# eMMC.net
KiCad netlist of a schematic drawn in Altium Designer
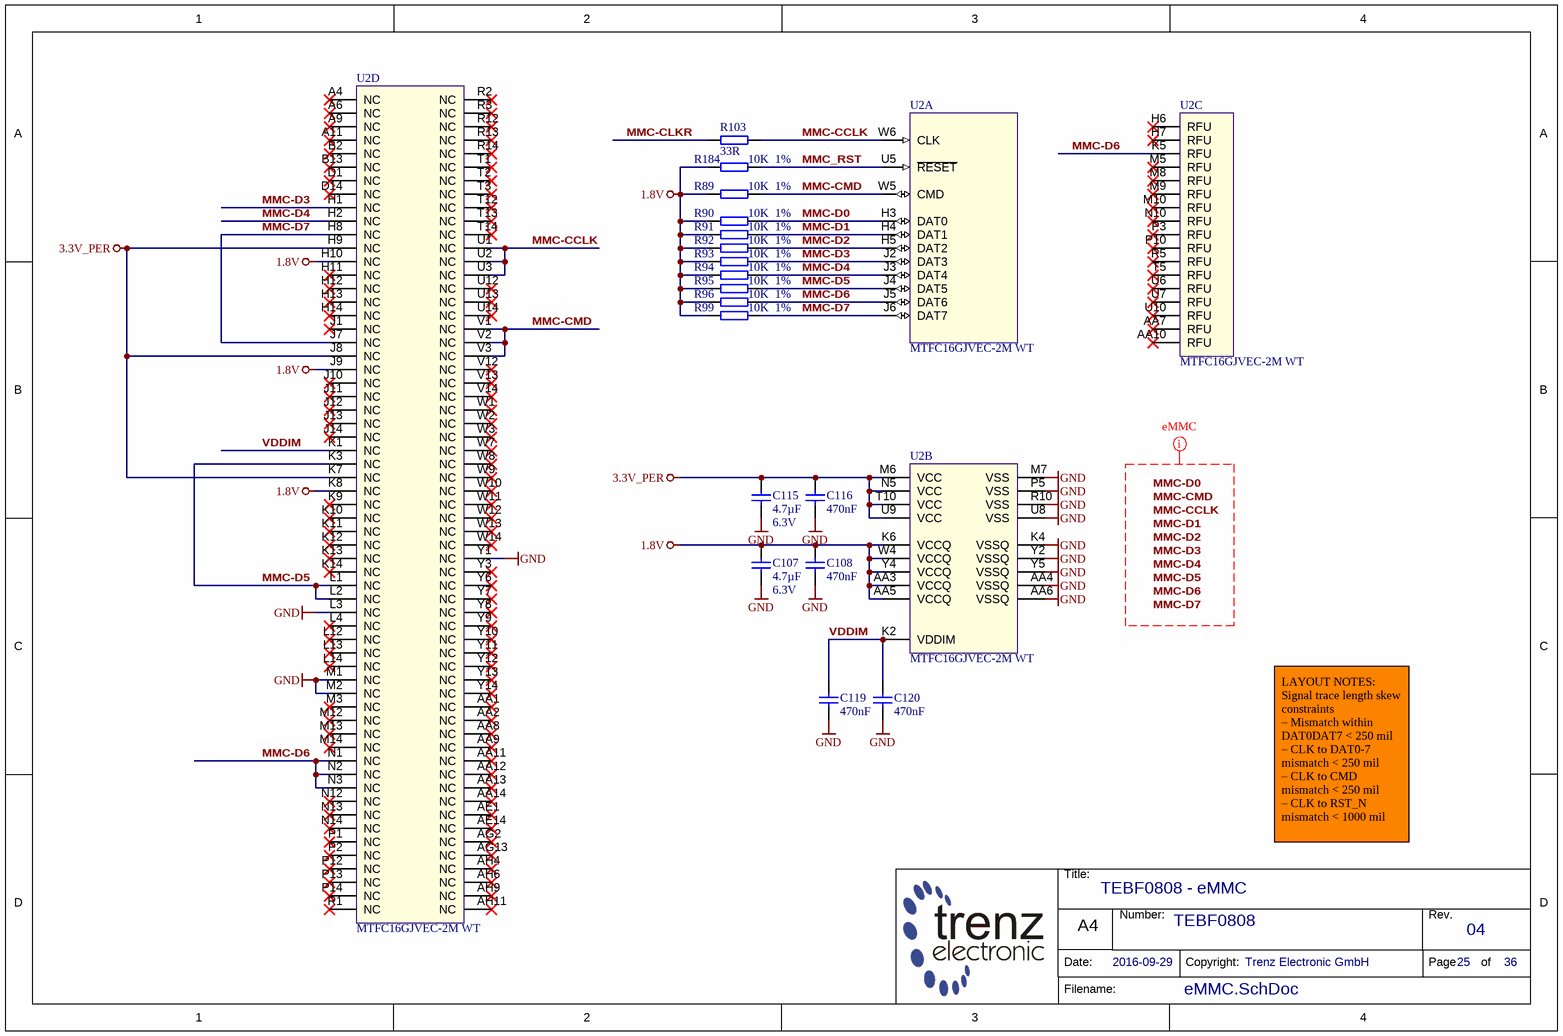
[diagram p0: eMMC.SchDoc]

(export (version "E")
  (design (tool "Eeschema 10.0.6"))
  (components
    (comp (ref "C107")
      (value "4.7µF")
      (footprint "CAPC1005X60N")
      (description "KON 4.7µF 6.3V X5R SMD 20%")
      (fields (field (name "VOLTAGE") "6.3V") (field (name "TOLERANCE") "20%"))
      (libsource (lib "TE") (part "CAP-NP"))
    )
    (comp (ref "C108")
      (value "470nF")
      (footprint "CAPC1005X55N")
      (description "KON 470nF 6,3V X5R SMD")
      (fields (field (name "VOLTAGE") "6.3V"))
      (libsource (lib "TE") (part "CAP-NP"))
    )
    (comp (ref "C115")
      (value "4.7µF")
      (footprint "CAPC1005X60N")
      (description "KON 4.7µF 6.3V X5R SMD 20%")
      (fields (field (name "VOLTAGE") "6.3V") (field (name "TOLERANCE") "20%"))
      (libsource (lib "TE") (part "CAP-NP"))
    )
    (comp (ref "C116")
      (value "470nF")
      (footprint "CAPC1005X55N")
      (description "KON 470nF 6,3V X5R SMD")
      (fields (field (name "VOLTAGE") "6.3V"))
      (libsource (lib "TE") (part "CAP-NP"))
    )
    (comp (ref "C119")
      (value "470nF")
      (footprint "CAPC1005X55N")
      (description "KON 470nF 6,3V X5R SMD")
      (fields (field (name "VOLTAGE") "6.3V"))
      (libsource (lib "TE") (part "CAP-NP"))
    )
    (comp (ref "C120")
      (value "470nF")
      (footprint "CAPC1005X55N")
      (description "KON 470nF 6,3V X5R SMD")
      (fields (field (name "VOLTAGE") "6.3V"))
      (libsource (lib "TE") (part "CAP-NP"))
    )
    (comp (ref "R89")
      (value "10K")
      (footprint "RESC1005X40N")
      (description "WID SMD 10K 1% 0,063W")
      (fields (field (name "TOLERANCE") "1%"))
      (libsource (lib "TE") (part "RES"))
    )
    (comp (ref "R90")
      (value "10K")
      (footprint "RESC1005X40N")
      (description "WID SMD 10K 1% 0,063W")
      (fields (field (name "TOLERANCE") "1%"))
      (libsource (lib "TE") (part "RES"))
    )
    (comp (ref "R91")
      (value "10K")
      (footprint "RESC1005X40N")
      (description "WID SMD 10K 1% 0,063W")
      (fields (field (name "TOLERANCE") "1%"))
      (libsource (lib "TE") (part "RES"))
    )
    (comp (ref "R92")
      (value "10K")
      (footprint "RESC1005X40N")
      (description "WID SMD 10K 1% 0,063W")
      (fields (field (name "TOLERANCE") "1%"))
      (libsource (lib "TE") (part "RES"))
    )
    (comp (ref "R93")
      (value "10K")
      (footprint "RESC1005X40N")
      (description "WID SMD 10K 1% 0,063W")
      (fields (field (name "TOLERANCE") "1%"))
      (libsource (lib "TE") (part "RES"))
    )
    (comp (ref "R94")
      (value "10K")
      (footprint "RESC1005X40N")
      (description "WID SMD 10K 1% 0,063W")
      (fields (field (name "TOLERANCE") "1%"))
      (libsource (lib "TE") (part "RES"))
    )
    (comp (ref "R95")
      (value "10K")
      (footprint "RESC1005X40N")
      (description "WID SMD 10K 1% 0,063W")
      (fields (field (name "TOLERANCE") "1%"))
      (libsource (lib "TE") (part "RES"))
    )
    (comp (ref "R96")
      (value "10K")
      (footprint "RESC1005X40N")
      (description "WID SMD 10K 1% 0,063W")
      (fields (field (name "TOLERANCE") "1%"))
      (libsource (lib "TE") (part "RES"))
    )
    (comp (ref "R99")
      (value "10K")
      (footprint "RESC1005X40N")
      (description "WID SMD 10K 1% 0,063W")
      (fields (field (name "TOLERANCE") "1%"))
      (libsource (lib "TE") (part "RES"))
    )
    (comp (ref "R103")
      (value "33R")
      (footprint "RESC1005X40N")
      (description "WID SMD 33R 1% 0,063W")
      (fields (field (name "TOLERANCE") "1%"))
      (libsource (lib "TE") (part "RES"))
    )
    (comp (ref "R184")
      (value "10K")
      (footprint "RESC1005X40N")
      (description "WID SMD 10K 1% 0,063W")
      (fields (field (name "TOLERANCE") "1%"))
      (libsource (lib "TE") (part "RES"))
    )
    (comp (ref "U2")
      (value "MTFC16GJVEC-2M WT")
      (footprint "BGA169C50P14X28_1400X1800X80_MICRON")
      (libsource (lib "TE") (part "MTFC-WFBGA169"))
    )
  )
  (nets
    (net (code "1") (name "/MMC-CCLK") (class "Default")
      (node (ref "R103") (pin "2") (pinfunction "2_2") (pintype "passive"))
      (node (ref "U2") (pin "U1") (pinfunction "NC_U1") (pintype "passive"))
      (node (ref "U2") (pin "U2") (pinfunction "NC_U2") (pintype "passive"))
      (node (ref "U2") (pin "U3") (pinfunction "NC_U3") (pintype "passive"))
      (node (ref "U2") (pin "W6") (pinfunction "CLK_W6") (pintype "input"))
    )
    (net (code "2") (name "/MMC-CLKR") (class "Default")
      (node (ref "R103") (pin "1") (pinfunction "1_1") (pintype "passive"))
    )
    (net (code "3") (name "/MMC-CMD") (class "Default")
      (node (ref "R89") (pin "2") (pinfunction "2_2") (pintype "passive"))
      (node (ref "U2") (pin "V1") (pinfunction "NC_V1") (pintype "passive"))
      (node (ref "U2") (pin "V2") (pinfunction "NC_V2") (pintype "passive"))
      (node (ref "U2") (pin "V3") (pinfunction "NC_V3") (pintype "passive"))
      (node (ref "U2") (pin "W5") (pinfunction "CMD_W5") (pintype "bidirectional"))
    )
    (net (code "4") (name "/MMC-D0") (class "Default")
      (node (ref "R90") (pin "2") (pinfunction "2_2") (pintype "passive"))
      (node (ref "U2") (pin "H3") (pinfunction "DAT0_H3") (pintype "bidirectional"))
    )
    (net (code "5") (name "/MMC-D1") (class "Default")
      (node (ref "R91") (pin "2") (pinfunction "2_2") (pintype "passive"))
      (node (ref "U2") (pin "H4") (pinfunction "DAT1_H4") (pintype "bidirectional"))
    )
    (net (code "6") (name "/MMC-D2") (class "Default")
      (node (ref "R92") (pin "2") (pinfunction "2_2") (pintype "passive"))
      (node (ref "U2") (pin "H5") (pinfunction "DAT2_H5") (pintype "bidirectional"))
    )
    (net (code "7") (name "/MMC-D3") (class "Default")
      (node (ref "R93") (pin "2") (pinfunction "2_2") (pintype "passive"))
      (node (ref "U2") (pin "H1") (pinfunction "NC_H1") (pintype "passive"))
      (node (ref "U2") (pin "J2") (pinfunction "DAT3_J2") (pintype "bidirectional"))
    )
    (net (code "8") (name "/MMC-D4") (class "Default")
      (node (ref "R94") (pin "2") (pinfunction "2_2") (pintype "passive"))
      (node (ref "U2") (pin "H2") (pinfunction "NC_H2") (pintype "passive"))
      (node (ref "U2") (pin "J3") (pinfunction "DAT4_J3") (pintype "bidirectional"))
    )
    (net (code "9") (name "/MMC-D5") (class "Default")
      (node (ref "R95") (pin "2") (pinfunction "2_2") (pintype "passive"))
      (node (ref "U2") (pin "J4") (pinfunction "DAT5_J4") (pintype "bidirectional"))
      (node (ref "U2") (pin "K3") (pinfunction "NC_K3") (pintype "passive"))
      (node (ref "U2") (pin "L1") (pinfunction "NC_L1") (pintype "passive"))
      (node (ref "U2") (pin "L2") (pinfunction "NC_L2") (pintype "passive"))
    )
    (net (code "10") (name "/MMC-D6") (class "Default")
      (node (ref "R96") (pin "2") (pinfunction "2_2") (pintype "passive"))
      (node (ref "U2") (pin "J5") (pinfunction "DAT6_J5") (pintype "bidirectional"))
      (node (ref "U2") (pin "K5") (pinfunction "RFU_K5") (pintype "passive"))
      (node (ref "U2") (pin "N1") (pinfunction "NC_N1") (pintype "passive"))
      (node (ref "U2") (pin "N2") (pinfunction "NC_N2") (pintype "passive"))
      (node (ref "U2") (pin "N3") (pinfunction "NC_N3") (pintype "passive"))
    )
    (net (code "11") (name "/MMC-D7") (class "Default")
      (node (ref "R99") (pin "2") (pinfunction "2_2") (pintype "passive"))
      (node (ref "U2") (pin "H8") (pinfunction "NC_H8") (pintype "passive"))
      (node (ref "U2") (pin "J6") (pinfunction "DAT7_J6") (pintype "bidirectional"))
      (node (ref "U2") (pin "J7") (pinfunction "NC_J7") (pintype "passive"))
    )
    (net (code "12") (name "/MMC_RST") (class "Default")
      (node (ref "R184") (pin "2") (pinfunction "2_2") (pintype "passive"))
      (node (ref "U2") (pin "U5") (pinfunction "~{RESET}_U5") (pintype "input"))
    )
    (net (code "13") (name "/VDDIM") (class "Default")
      (node (ref "C119") (pin "1") (pinfunction "1_1") (pintype "passive"))
      (node (ref "C120") (pin "1") (pinfunction "1_1") (pintype "passive"))
      (node (ref "U2") (pin "K1") (pinfunction "NC_K1") (pintype "passive"))
      (node (ref "U2") (pin "K2") (pinfunction "VDDIM_K2") (pintype "power_in"))
    )
    (net (code "14") (name "1.8V") (class "Default")
      (node (ref "C107") (pin "1") (pinfunction "1_1") (pintype "passive"))
      (node (ref "C108") (pin "1") (pinfunction "1_1") (pintype "passive"))
      (node (ref "R184") (pin "1") (pinfunction "1_1") (pintype "passive"))
      (node (ref "R89") (pin "1") (pinfunction "1_1") (pintype "passive"))
      (node (ref "R90") (pin "1") (pinfunction "1_1") (pintype "passive"))
      (node (ref "R91") (pin "1") (pinfunction "1_1") (pintype "passive"))
      (node (ref "R92") (pin "1") (pinfunction "1_1") (pintype "passive"))
      (node (ref "R93") (pin "1") (pinfunction "1_1") (pintype "passive"))
      (node (ref "R94") (pin "1") (pinfunction "1_1") (pintype "passive"))
      (node (ref "R95") (pin "1") (pinfunction "1_1") (pintype "passive"))
      (node (ref "R96") (pin "1") (pinfunction "1_1") (pintype "passive"))
      (node (ref "R99") (pin "1") (pinfunction "1_1") (pintype "passive"))
      (node (ref "U2") (pin "AA3") (pinfunction "VCCQ_AA3") (pintype "power_in"))
      (node (ref "U2") (pin "AA5") (pinfunction "VCCQ_AA5") (pintype "power_in"))
      (node (ref "U2") (pin "H10") (pinfunction "NC_H10") (pintype "passive"))
      (node (ref "U2") (pin "J9") (pinfunction "NC_J9") (pintype "passive"))
      (node (ref "U2") (pin "K6") (pinfunction "VCCQ_K6") (pintype "power_in"))
      (node (ref "U2") (pin "K8") (pinfunction "NC_K8") (pintype "passive"))
      (node (ref "U2") (pin "W4") (pinfunction "VCCQ_W4") (pintype "power_in"))
      (node (ref "U2") (pin "Y4") (pinfunction "VCCQ_Y4") (pintype "power_in"))
    )
    (net (code "15") (name "3.3V_PER") (class "Default")
      (node (ref "C115") (pin "1") (pinfunction "1_1") (pintype "passive"))
      (node (ref "C116") (pin "1") (pinfunction "1_1") (pintype "passive"))
      (node (ref "U2") (pin "H9") (pinfunction "NC_H9") (pintype "passive"))
      (node (ref "U2") (pin "J8") (pinfunction "NC_J8") (pintype "passive"))
      (node (ref "U2") (pin "K7") (pinfunction "NC_K7") (pintype "passive"))
      (node (ref "U2") (pin "M6") (pinfunction "VCC_M6") (pintype "power_in"))
      (node (ref "U2") (pin "N5") (pinfunction "VCC_N5") (pintype "power_in"))
      (node (ref "U2") (pin "T10") (pinfunction "VCC_T10") (pintype "power_in"))
      (node (ref "U2") (pin "U9") (pinfunction "VCC_U9") (pintype "power_in"))
    )
    (net (code "16") (name "GND") (class "Default")
      (node (ref "C107") (pin "2") (pinfunction "2_2") (pintype "passive"))
      (node (ref "C108") (pin "2") (pinfunction "2_2") (pintype "passive"))
      (node (ref "C115") (pin "2") (pinfunction "2_2") (pintype "passive"))
      (node (ref "C116") (pin "2") (pinfunction "2_2") (pintype "passive"))
      (node (ref "C119") (pin "2") (pinfunction "2_2") (pintype "passive"))
      (node (ref "C120") (pin "2") (pinfunction "2_2") (pintype "passive"))
      (node (ref "U2") (pin "AA4") (pinfunction "VSSQ_AA4") (pintype "power_in"))
      (node (ref "U2") (pin "AA6") (pinfunction "VSSQ_AA6") (pintype "power_in"))
      (node (ref "U2") (pin "K4") (pinfunction "VSSQ_K4") (pintype "power_in"))
      (node (ref "U2") (pin "L3") (pinfunction "NC_L3") (pintype "passive"))
      (node (ref "U2") (pin "M1") (pinfunction "NC_M1") (pintype "passive"))
      (node (ref "U2") (pin "M2") (pinfunction "NC_M2") (pintype "passive"))
      (node (ref "U2") (pin "M7") (pinfunction "VSS_M7") (pintype "power_in"))
      (node (ref "U2") (pin "P5") (pinfunction "VSS_P5") (pintype "power_in"))
      (node (ref "U2") (pin "R10") (pinfunction "VSS_R10") (pintype "power_in"))
      (node (ref "U2") (pin "U8") (pinfunction "VSS_U8") (pintype "power_in"))
      (node (ref "U2") (pin "Y1") (pinfunction "NC_Y1") (pintype "passive"))
      (node (ref "U2") (pin "Y2") (pinfunction "VSSQ_Y2") (pintype "power_in"))
      (node (ref "U2") (pin "Y5") (pinfunction "VSSQ_Y5") (pintype "power_in"))
    )
    (net (code "17") (name "unconnected-(U2C-RFU-PadAA7)") (class "Default")
      (node (ref "U2") (pin "AA7") (pinfunction "RFU_AA7") (pintype "passive+no_connect"))
    )
    (net (code "18") (name "unconnected-(U2C-RFU-PadAA10)") (class "Default")
      (node (ref "U2") (pin "AA10") (pinfunction "RFU_AA10") (pintype "passive+no_connect"))
    )
    (net (code "19") (name "unconnected-(U2C-RFU-PadH6)") (class "Default")
      (node (ref "U2") (pin "H6") (pinfunction "RFU_H6") (pintype "passive+no_connect"))
    )
    (net (code "20") (name "unconnected-(U2C-RFU-PadH7)") (class "Default")
      (node (ref "U2") (pin "H7") (pinfunction "RFU_H7") (pintype "passive+no_connect"))
    )
    (net (code "21") (name "unconnected-(U2C-RFU-PadM5)") (class "Default")
      (node (ref "U2") (pin "M5") (pinfunction "RFU_M5") (pintype "passive+no_connect"))
    )
    (net (code "22") (name "unconnected-(U2C-RFU-PadM8)") (class "Default")
      (node (ref "U2") (pin "M8") (pinfunction "RFU_M8") (pintype "passive+no_connect"))
    )
    (net (code "23") (name "unconnected-(U2C-RFU-PadM9)") (class "Default")
      (node (ref "U2") (pin "M9") (pinfunction "RFU_M9") (pintype "passive+no_connect"))
    )
    (net (code "24") (name "unconnected-(U2C-RFU-PadM10)") (class "Default")
      (node (ref "U2") (pin "M10") (pinfunction "RFU_M10") (pintype "passive+no_connect"))
    )
    (net (code "25") (name "unconnected-(U2C-RFU-PadN10)") (class "Default")
      (node (ref "U2") (pin "N10") (pinfunction "RFU_N10") (pintype "passive+no_connect"))
    )
    (net (code "26") (name "unconnected-(U2C-RFU-PadP3)") (class "Default")
      (node (ref "U2") (pin "P3") (pinfunction "RFU_P3") (pintype "passive+no_connect"))
    )
    (net (code "27") (name "unconnected-(U2C-RFU-PadP10)") (class "Default")
      (node (ref "U2") (pin "P10") (pinfunction "RFU_P10") (pintype "passive+no_connect"))
    )
    (net (code "28") (name "unconnected-(U2C-RFU-PadR5)") (class "Default")
      (node (ref "U2") (pin "R5") (pinfunction "RFU_R5") (pintype "passive+no_connect"))
    )
    (net (code "29") (name "unconnected-(U2C-RFU-PadT5)") (class "Default")
      (node (ref "U2") (pin "T5") (pinfunction "RFU_T5") (pintype "passive+no_connect"))
    )
    (net (code "30") (name "unconnected-(U2C-RFU-PadU6)") (class "Default")
      (node (ref "U2") (pin "U6") (pinfunction "RFU_U6") (pintype "passive+no_connect"))
    )
    (net (code "31") (name "unconnected-(U2C-RFU-PadU7)") (class "Default")
      (node (ref "U2") (pin "U7") (pinfunction "RFU_U7") (pintype "passive+no_connect"))
    )
    (net (code "32") (name "unconnected-(U2C-RFU-PadU10)") (class "Default")
      (node (ref "U2") (pin "U10") (pinfunction "RFU_U10") (pintype "passive+no_connect"))
    )
    (net (code "33") (name "unconnected-(U2D-NC-PadA4)") (class "Default")
      (node (ref "U2") (pin "A4") (pinfunction "NC_A4") (pintype "passive+no_connect"))
    )
    (net (code "34") (name "unconnected-(U2D-NC-PadA6)") (class "Default")
      (node (ref "U2") (pin "A6") (pinfunction "NC_A6") (pintype "passive+no_connect"))
    )
    (net (code "35") (name "unconnected-(U2D-NC-PadA9)") (class "Default")
      (node (ref "U2") (pin "A9") (pinfunction "NC_A9") (pintype "passive+no_connect"))
    )
    (net (code "36") (name "unconnected-(U2D-NC-PadA11)") (class "Default")
      (node (ref "U2") (pin "A11") (pinfunction "NC_A11") (pintype "passive+no_connect"))
    )
    (net (code "37") (name "unconnected-(U2D-NC-PadAA1)") (class "Default")
      (node (ref "U2") (pin "AA1") (pinfunction "NC_AA1") (pintype "passive+no_connect"))
    )
    (net (code "38") (name "unconnected-(U2D-NC-PadAA2)") (class "Default")
      (node (ref "U2") (pin "AA2") (pinfunction "NC_AA2") (pintype "passive+no_connect"))
    )
    (net (code "39") (name "unconnected-(U2D-NC-PadAA8)") (class "Default")
      (node (ref "U2") (pin "AA8") (pinfunction "NC_AA8") (pintype "passive+no_connect"))
    )
    (net (code "40") (name "unconnected-(U2D-NC-PadAA9)") (class "Default")
      (node (ref "U2") (pin "AA9") (pinfunction "NC_AA9") (pintype "passive+no_connect"))
    )
    (net (code "41") (name "unconnected-(U2D-NC-PadAA11)") (class "Default")
      (node (ref "U2") (pin "AA11") (pinfunction "NC_AA11") (pintype "passive+no_connect"))
    )
    (net (code "42") (name "unconnected-(U2D-NC-PadAA12)") (class "Default")
      (node (ref "U2") (pin "AA12") (pinfunction "NC_AA12") (pintype "passive+no_connect"))
    )
    (net (code "43") (name "unconnected-(U2D-NC-PadAA13)") (class "Default")
      (node (ref "U2") (pin "AA13") (pinfunction "NC_AA13") (pintype "passive+no_connect"))
    )
    (net (code "44") (name "unconnected-(U2D-NC-PadAA14)") (class "Default")
      (node (ref "U2") (pin "AA14") (pinfunction "NC_AA14") (pintype "passive+no_connect"))
    )
    (net (code "45") (name "unconnected-(U2D-NC-PadAE1)") (class "Default")
      (node (ref "U2") (pin "AE1") (pinfunction "NC_AE1") (pintype "passive+no_connect"))
    )
    (net (code "46") (name "unconnected-(U2D-NC-PadAE14)") (class "Default")
      (node (ref "U2") (pin "AE14") (pinfunction "NC_AE14") (pintype "passive+no_connect"))
    )
    (net (code "47") (name "unconnected-(U2D-NC-PadAG2)") (class "Default")
      (node (ref "U2") (pin "AG2") (pinfunction "NC_AG2") (pintype "passive+no_connect"))
    )
    (net (code "48") (name "unconnected-(U2D-NC-PadAG13)") (class "Default")
      (node (ref "U2") (pin "AG13") (pinfunction "NC_AG13") (pintype "passive+no_connect"))
    )
    (net (code "49") (name "unconnected-(U2D-NC-PadAH4)") (class "Default")
      (node (ref "U2") (pin "AH4") (pinfunction "NC_AH4") (pintype "passive+no_connect"))
    )
    (net (code "50") (name "unconnected-(U2D-NC-PadAH6)") (class "Default")
      (node (ref "U2") (pin "AH6") (pinfunction "NC_AH6") (pintype "passive+no_connect"))
    )
    (net (code "51") (name "unconnected-(U2D-NC-PadAH9)") (class "Default")
      (node (ref "U2") (pin "AH9") (pinfunction "NC_AH9") (pintype "passive+no_connect"))
    )
    (net (code "52") (name "unconnected-(U2D-NC-PadAH11)") (class "Default")
      (node (ref "U2") (pin "AH11") (pinfunction "NC_AH11") (pintype "passive+no_connect"))
    )
    (net (code "53") (name "unconnected-(U2D-NC-PadB2)") (class "Default")
      (node (ref "U2") (pin "B2") (pinfunction "NC_B2") (pintype "passive+no_connect"))
    )
    (net (code "54") (name "unconnected-(U2D-NC-PadB13)") (class "Default")
      (node (ref "U2") (pin "B13") (pinfunction "NC_B13") (pintype "passive+no_connect"))
    )
    (net (code "55") (name "unconnected-(U2D-NC-PadD1)") (class "Default")
      (node (ref "U2") (pin "D1") (pinfunction "NC_D1") (pintype "passive+no_connect"))
    )
    (net (code "56") (name "unconnected-(U2D-NC-PadD14)") (class "Default")
      (node (ref "U2") (pin "D14") (pinfunction "NC_D14") (pintype "passive+no_connect"))
    )
    (net (code "57") (name "unconnected-(U2D-NC-PadH11)") (class "Default")
      (node (ref "U2") (pin "H11") (pinfunction "NC_H11") (pintype "passive+no_connect"))
    )
    (net (code "58") (name "unconnected-(U2D-NC-PadH12)") (class "Default")
      (node (ref "U2") (pin "H12") (pinfunction "NC_H12") (pintype "passive+no_connect"))
    )
    (net (code "59") (name "unconnected-(U2D-NC-PadH13)") (class "Default")
      (node (ref "U2") (pin "H13") (pinfunction "NC_H13") (pintype "passive+no_connect"))
    )
    (net (code "60") (name "unconnected-(U2D-NC-PadH14)") (class "Default")
      (node (ref "U2") (pin "H14") (pinfunction "NC_H14") (pintype "passive+no_connect"))
    )
    (net (code "61") (name "unconnected-(U2D-NC-PadJ1)") (class "Default")
      (node (ref "U2") (pin "J1") (pinfunction "NC_J1") (pintype "passive+no_connect"))
    )
    (net (code "62") (name "unconnected-(U2D-NC-PadJ10)") (class "Default")
      (node (ref "U2") (pin "J10") (pinfunction "NC_J10") (pintype "passive+no_connect"))
    )
    (net (code "63") (name "unconnected-(U2D-NC-PadJ11)") (class "Default")
      (node (ref "U2") (pin "J11") (pinfunction "NC_J11") (pintype "passive+no_connect"))
    )
    (net (code "64") (name "unconnected-(U2D-NC-PadJ12)") (class "Default")
      (node (ref "U2") (pin "J12") (pinfunction "NC_J12") (pintype "passive+no_connect"))
    )
    (net (code "65") (name "unconnected-(U2D-NC-PadJ13)") (class "Default")
      (node (ref "U2") (pin "J13") (pinfunction "NC_J13") (pintype "passive+no_connect"))
    )
    (net (code "66") (name "unconnected-(U2D-NC-PadJ14)") (class "Default")
      (node (ref "U2") (pin "J14") (pinfunction "NC_J14") (pintype "passive+no_connect"))
    )
    (net (code "67") (name "unconnected-(U2D-NC-PadK9)") (class "Default")
      (node (ref "U2") (pin "K9") (pinfunction "NC_K9") (pintype "passive+no_connect"))
    )
    (net (code "68") (name "unconnected-(U2D-NC-PadK10)") (class "Default")
      (node (ref "U2") (pin "K10") (pinfunction "NC_K10") (pintype "passive+no_connect"))
    )
    (net (code "69") (name "unconnected-(U2D-NC-PadK11)") (class "Default")
      (node (ref "U2") (pin "K11") (pinfunction "NC_K11") (pintype "passive+no_connect"))
    )
    (net (code "70") (name "unconnected-(U2D-NC-PadK12)") (class "Default")
      (node (ref "U2") (pin "K12") (pinfunction "NC_K12") (pintype "passive+no_connect"))
    )
    (net (code "71") (name "unconnected-(U2D-NC-PadK13)") (class "Default")
      (node (ref "U2") (pin "K13") (pinfunction "NC_K13") (pintype "passive+no_connect"))
    )
    (net (code "72") (name "unconnected-(U2D-NC-PadK14)") (class "Default")
      (node (ref "U2") (pin "K14") (pinfunction "NC_K14") (pintype "passive+no_connect"))
    )
    (net (code "73") (name "unconnected-(U2D-NC-PadL4)") (class "Default")
      (node (ref "U2") (pin "L4") (pinfunction "NC_L4") (pintype "passive+no_connect"))
    )
    (net (code "74") (name "unconnected-(U2D-NC-PadL12)") (class "Default")
      (node (ref "U2") (pin "L12") (pinfunction "NC_L12") (pintype "passive+no_connect"))
    )
    (net (code "75") (name "unconnected-(U2D-NC-PadL13)") (class "Default")
      (node (ref "U2") (pin "L13") (pinfunction "NC_L13") (pintype "passive+no_connect"))
    )
    (net (code "76") (name "unconnected-(U2D-NC-PadL14)") (class "Default")
      (node (ref "U2") (pin "L14") (pinfunction "NC_L14") (pintype "passive+no_connect"))
    )
    (net (code "77") (name "unconnected-(U2D-NC-PadM3)") (class "Default")
      (node (ref "U2") (pin "M3") (pinfunction "NC_M3") (pintype "passive+no_connect"))
    )
    (net (code "78") (name "unconnected-(U2D-NC-PadM12)") (class "Default")
      (node (ref "U2") (pin "M12") (pinfunction "NC_M12") (pintype "passive+no_connect"))
    )
    (net (code "79") (name "unconnected-(U2D-NC-PadM13)") (class "Default")
      (node (ref "U2") (pin "M13") (pinfunction "NC_M13") (pintype "passive+no_connect"))
    )
    (net (code "80") (name "unconnected-(U2D-NC-PadM14)") (class "Default")
      (node (ref "U2") (pin "M14") (pinfunction "NC_M14") (pintype "passive+no_connect"))
    )
    (net (code "81") (name "unconnected-(U2D-NC-PadN12)") (class "Default")
      (node (ref "U2") (pin "N12") (pinfunction "NC_N12") (pintype "passive+no_connect"))
    )
    (net (code "82") (name "unconnected-(U2D-NC-PadN13)") (class "Default")
      (node (ref "U2") (pin "N13") (pinfunction "NC_N13") (pintype "passive+no_connect"))
    )
    (net (code "83") (name "unconnected-(U2D-NC-PadN14)") (class "Default")
      (node (ref "U2") (pin "N14") (pinfunction "NC_N14") (pintype "passive+no_connect"))
    )
    (net (code "84") (name "unconnected-(U2D-NC-PadP1)") (class "Default")
      (node (ref "U2") (pin "P1") (pinfunction "NC_P1") (pintype "passive+no_connect"))
    )
    (net (code "85") (name "unconnected-(U2D-NC-PadP2)") (class "Default")
      (node (ref "U2") (pin "P2") (pinfunction "NC_P2") (pintype "passive+no_connect"))
    )
    (net (code "86") (name "unconnected-(U2D-NC-PadP12)") (class "Default")
      (node (ref "U2") (pin "P12") (pinfunction "NC_P12") (pintype "passive+no_connect"))
    )
    (net (code "87") (name "unconnected-(U2D-NC-PadP13)") (class "Default")
      (node (ref "U2") (pin "P13") (pinfunction "NC_P13") (pintype "passive+no_connect"))
    )
    (net (code "88") (name "unconnected-(U2D-NC-PadP14)") (class "Default")
      (node (ref "U2") (pin "P14") (pinfunction "NC_P14") (pintype "passive+no_connect"))
    )
    (net (code "89") (name "unconnected-(U2D-NC-PadR1)") (class "Default")
      (node (ref "U2") (pin "R1") (pinfunction "NC_R1") (pintype "passive+no_connect"))
    )
    (net (code "90") (name "unconnected-(U2D-NC-PadR2)") (class "Default")
      (node (ref "U2") (pin "R2") (pinfunction "NC_R2") (pintype "passive+no_connect"))
    )
    (net (code "91") (name "unconnected-(U2D-NC-PadR3)") (class "Default")
      (node (ref "U2") (pin "R3") (pinfunction "NC_R3") (pintype "passive+no_connect"))
    )
    (net (code "92") (name "unconnected-(U2D-NC-PadR12)") (class "Default")
      (node (ref "U2") (pin "R12") (pinfunction "NC_R12") (pintype "passive+no_connect"))
    )
    (net (code "93") (name "unconnected-(U2D-NC-PadR13)") (class "Default")
      (node (ref "U2") (pin "R13") (pinfunction "NC_R13") (pintype "passive+no_connect"))
    )
    (net (code "94") (name "unconnected-(U2D-NC-PadR14)") (class "Default")
      (node (ref "U2") (pin "R14") (pinfunction "NC_R14") (pintype "passive+no_connect"))
    )
    (net (code "95") (name "unconnected-(U2D-NC-PadT1)") (class "Default")
      (node (ref "U2") (pin "T1") (pinfunction "NC_T1") (pintype "passive+no_connect"))
    )
    (net (code "96") (name "unconnected-(U2D-NC-PadT2)") (class "Default")
      (node (ref "U2") (pin "T2") (pinfunction "NC_T2") (pintype "passive+no_connect"))
    )
    (net (code "97") (name "unconnected-(U2D-NC-PadT3)") (class "Default")
      (node (ref "U2") (pin "T3") (pinfunction "NC_T3") (pintype "passive+no_connect"))
    )
    (net (code "98") (name "unconnected-(U2D-NC-PadT12)") (class "Default")
      (node (ref "U2") (pin "T12") (pinfunction "NC_T12") (pintype "passive+no_connect"))
    )
    (net (code "99") (name "unconnected-(U2D-NC-PadT13)") (class "Default")
      (node (ref "U2") (pin "T13") (pinfunction "NC_T13") (pintype "passive+no_connect"))
    )
    (net (code "100") (name "unconnected-(U2D-NC-PadT14)") (class "Default")
      (node (ref "U2") (pin "T14") (pinfunction "NC_T14") (pintype "passive+no_connect"))
    )
    (net (code "101") (name "unconnected-(U2D-NC-PadU12)") (class "Default")
      (node (ref "U2") (pin "U12") (pinfunction "NC_U12") (pintype "passive+no_connect"))
    )
    (net (code "102") (name "unconnected-(U2D-NC-PadU13)") (class "Default")
      (node (ref "U2") (pin "U13") (pinfunction "NC_U13") (pintype "passive+no_connect"))
    )
    (net (code "103") (name "unconnected-(U2D-NC-PadU14)") (class "Default")
      (node (ref "U2") (pin "U14") (pinfunction "NC_U14") (pintype "passive+no_connect"))
    )
    (net (code "104") (name "unconnected-(U2D-NC-PadV12)") (class "Default")
      (node (ref "U2") (pin "V12") (pinfunction "NC_V12") (pintype "passive+no_connect"))
    )
    (net (code "105") (name "unconnected-(U2D-NC-PadV13)") (class "Default")
      (node (ref "U2") (pin "V13") (pinfunction "NC_V13") (pintype "passive+no_connect"))
    )
    (net (code "106") (name "unconnected-(U2D-NC-PadV14)") (class "Default")
      (node (ref "U2") (pin "V14") (pinfunction "NC_V14") (pintype "passive+no_connect"))
    )
    (net (code "107") (name "unconnected-(U2D-NC-PadW1)") (class "Default")
      (node (ref "U2") (pin "W1") (pinfunction "NC_W1") (pintype "passive+no_connect"))
    )
    (net (code "108") (name "unconnected-(U2D-NC-PadW2)") (class "Default")
      (node (ref "U2") (pin "W2") (pinfunction "NC_W2") (pintype "passive+no_connect"))
    )
    (net (code "109") (name "unconnected-(U2D-NC-PadW3)") (class "Default")
      (node (ref "U2") (pin "W3") (pinfunction "NC_W3") (pintype "passive+no_connect"))
    )
    (net (code "110") (name "unconnected-(U2D-NC-PadW7)") (class "Default")
      (node (ref "U2") (pin "W7") (pinfunction "NC_W7") (pintype "passive+no_connect"))
    )
    (net (code "111") (name "unconnected-(U2D-NC-PadW8)") (class "Default")
      (node (ref "U2") (pin "W8") (pinfunction "NC_W8") (pintype "passive+no_connect"))
    )
    (net (code "112") (name "unconnected-(U2D-NC-PadW9)") (class "Default")
      (node (ref "U2") (pin "W9") (pinfunction "NC_W9") (pintype "passive+no_connect"))
    )
    (net (code "113") (name "unconnected-(U2D-NC-PadW10)") (class "Default")
      (node (ref "U2") (pin "W10") (pinfunction "NC_W10") (pintype "passive+no_connect"))
    )
    (net (code "114") (name "unconnected-(U2D-NC-PadW11)") (class "Default")
      (node (ref "U2") (pin "W11") (pinfunction "NC_W11") (pintype "passive+no_connect"))
    )
    (net (code "115") (name "unconnected-(U2D-NC-PadW12)") (class "Default")
      (node (ref "U2") (pin "W12") (pinfunction "NC_W12") (pintype "passive+no_connect"))
    )
    (net (code "116") (name "unconnected-(U2D-NC-PadW13)") (class "Default")
      (node (ref "U2") (pin "W13") (pinfunction "NC_W13") (pintype "passive+no_connect"))
    )
    (net (code "117") (name "unconnected-(U2D-NC-PadW14)") (class "Default")
      (node (ref "U2") (pin "W14") (pinfunction "NC_W14") (pintype "passive+no_connect"))
    )
    (net (code "118") (name "unconnected-(U2D-NC-PadY3)") (class "Default")
      (node (ref "U2") (pin "Y3") (pinfunction "NC_Y3") (pintype "passive+no_connect"))
    )
    (net (code "119") (name "unconnected-(U2D-NC-PadY6)") (class "Default")
      (node (ref "U2") (pin "Y6") (pinfunction "NC_Y6") (pintype "passive+no_connect"))
    )
    (net (code "120") (name "unconnected-(U2D-NC-PadY7)") (class "Default")
      (node (ref "U2") (pin "Y7") (pinfunction "NC_Y7") (pintype "passive+no_connect"))
    )
    (net (code "121") (name "unconnected-(U2D-NC-PadY8)") (class "Default")
      (node (ref "U2") (pin "Y8") (pinfunction "NC_Y8") (pintype "passive+no_connect"))
    )
    (net (code "122") (name "unconnected-(U2D-NC-PadY9)") (class "Default")
      (node (ref "U2") (pin "Y9") (pinfunction "NC_Y9") (pintype "passive+no_connect"))
    )
    (net (code "123") (name "unconnected-(U2D-NC-PadY10)") (class "Default")
      (node (ref "U2") (pin "Y10") (pinfunction "NC_Y10") (pintype "passive+no_connect"))
    )
    (net (code "124") (name "unconnected-(U2D-NC-PadY11)") (class "Default")
      (node (ref "U2") (pin "Y11") (pinfunction "NC_Y11") (pintype "passive+no_connect"))
    )
    (net (code "125") (name "unconnected-(U2D-NC-PadY12)") (class "Default")
      (node (ref "U2") (pin "Y12") (pinfunction "NC_Y12") (pintype "passive+no_connect"))
    )
    (net (code "126") (name "unconnected-(U2D-NC-PadY13)") (class "Default")
      (node (ref "U2") (pin "Y13") (pinfunction "NC_Y13") (pintype "passive+no_connect"))
    )
    (net (code "127") (name "unconnected-(U2D-NC-PadY14)") (class "Default")
      (node (ref "U2") (pin "Y14") (pinfunction "NC_Y14") (pintype "passive+no_connect"))
    )
  )
)
